# UniBot-PW01_V1_0.net
KiCad netlist of a schematic drawn in Altium Designer
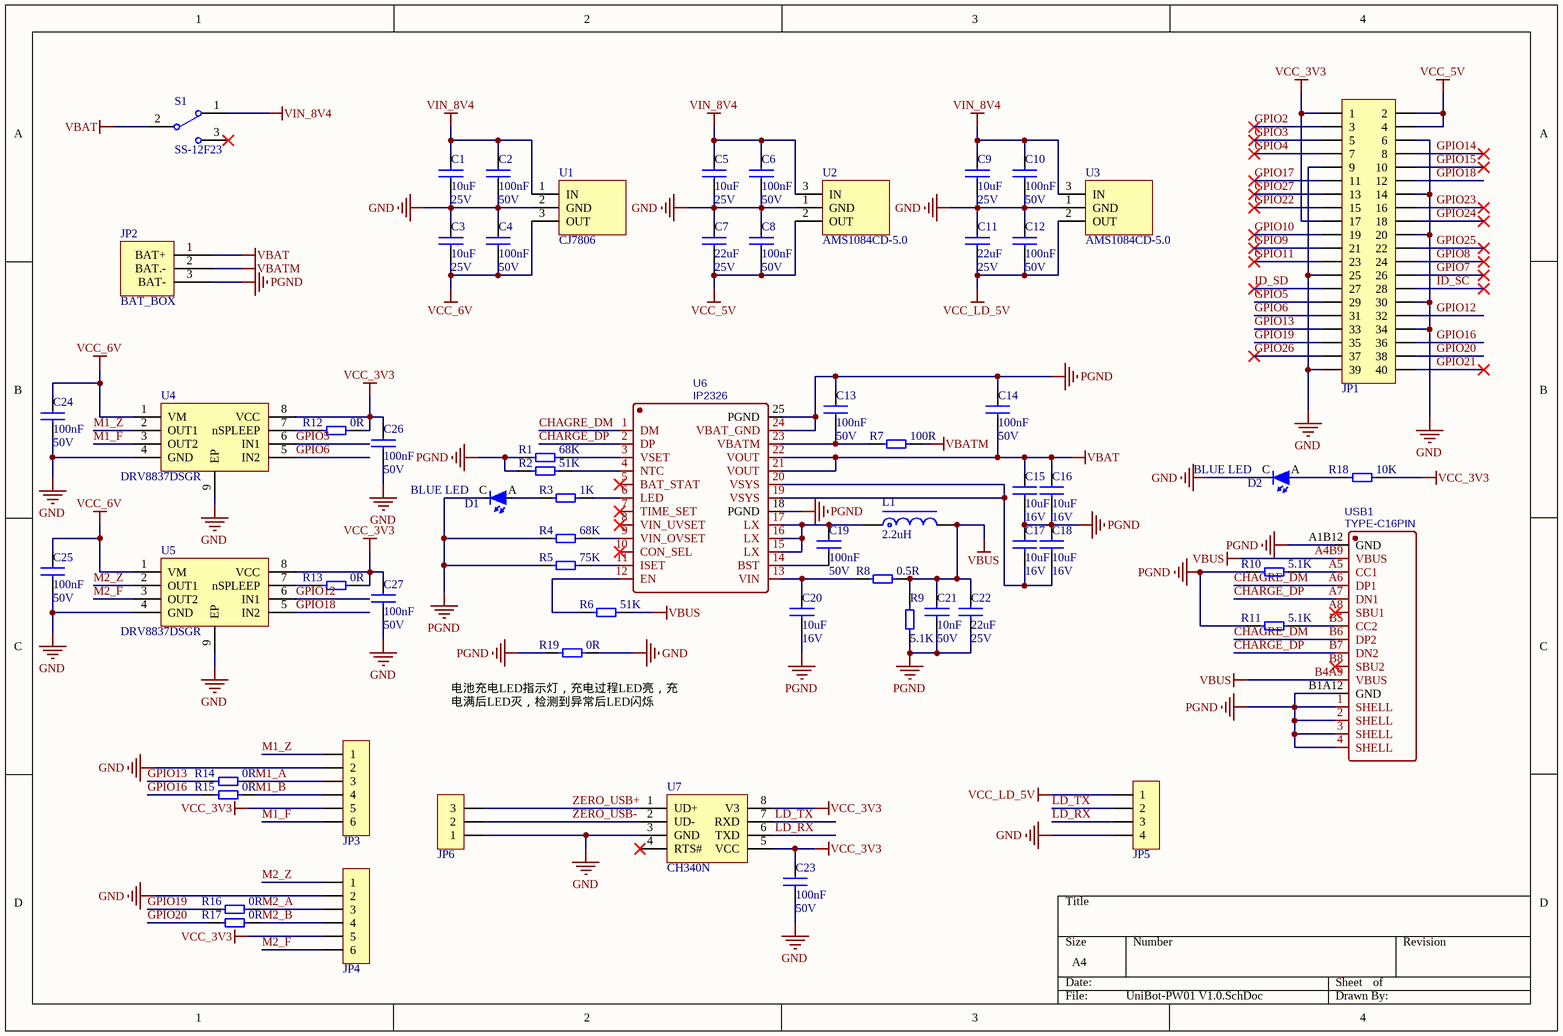
[diagram p0: UniBot-PW01 V1.0.SchDoc]

(export (version "E")
  (design (tool "Eeschema 10.0.6"))
  (components
    (comp (ref "C1")
      (value "10uF")
      (footprint "C0805")
      (description "CAP CER 10uF 25V X5R 0805")
      (fields
        (field (name "VOLTAGE") "25V")
        (field (name "PART NUMBER") "E01C00153")
        (field (name "POWER") "25V")
      )
      (libsource (lib "Database_Libs") (part "CAP NON POL"))
    )
    (comp (ref "C2")
      (value "100nF")
      (footprint "C0402")
      (description "CAP CER 100nF 50V X7R 0402")
      (fields
        (field (name "VOLTAGE") "50V")
        (field (name "PART NUMBER") "E01C00061")
        (field (name "POWER") "50V")
      )
      (libsource (lib "Database_Libs") (part "CAP NON POL"))
    )
    (comp (ref "C3")
      (value "10uF")
      (footprint "C0805")
      (description "CAP CER 10uF 25V X5R 0805")
      (fields
        (field (name "VOLTAGE") "25V")
        (field (name "PART NUMBER") "E01C00153")
        (field (name "POWER") "25V")
      )
      (libsource (lib "Database_Libs") (part "CAP NON POL"))
    )
    (comp (ref "C4")
      (value "100nF")
      (footprint "C0402")
      (description "CAP CER 100nF 50V X7R 0402")
      (fields
        (field (name "VOLTAGE") "50V")
        (field (name "PART NUMBER") "E01C00061")
        (field (name "POWER") "50V")
      )
      (libsource (lib "Database_Libs") (part "CAP NON POL"))
    )
    (comp (ref "C5")
      (value "10uF")
      (footprint "C0805")
      (description "CAP CER 10uF 25V X5R 0805")
      (fields
        (field (name "VOLTAGE") "25V")
        (field (name "PART NUMBER") "E01C00153")
        (field (name "POWER") "25V")
      )
      (libsource (lib "Database_Libs") (part "CAP NON POL"))
    )
    (comp (ref "C6")
      (value "100nF")
      (footprint "C0402")
      (description "CAP CER 100nF 50V X7R 0402")
      (fields
        (field (name "VOLTAGE") "50V")
        (field (name "PART NUMBER") "E01C00061")
        (field (name "POWER") "50V")
      )
      (libsource (lib "Database_Libs") (part "CAP NON POL"))
    )
    (comp (ref "C7")
      (value "22uF")
      (footprint "C0805")
      (description "CAP CER 22uF 25V X5R 0805")
      (fields
        (field (name "VOLTAGE") "25V")
        (field (name "PART NUMBER") "E01C00160")
        (field (name "POWER") "25V")
      )
      (libsource (lib "Database_Libs") (part "CAP NON POL"))
    )
    (comp (ref "C8")
      (value "100nF")
      (footprint "C0402")
      (description "CAP CER 100nF 50V X7R 0402")
      (fields
        (field (name "VOLTAGE") "50V")
        (field (name "PART NUMBER") "E01C00061")
        (field (name "POWER") "50V")
      )
      (libsource (lib "Database_Libs") (part "CAP NON POL"))
    )
    (comp (ref "C9")
      (value "10uF")
      (footprint "C0805")
      (description "CAP CER 10uF 25V X5R 0805")
      (fields
        (field (name "VOLTAGE") "25V")
        (field (name "PART NUMBER") "E01C00153")
        (field (name "POWER") "25V")
      )
      (libsource (lib "Database_Libs") (part "CAP NON POL"))
    )
    (comp (ref "C10")
      (value "100nF")
      (footprint "C0402")
      (description "CAP CER 100nF 50V X7R 0402")
      (fields
        (field (name "VOLTAGE") "50V")
        (field (name "PART NUMBER") "E01C00061")
        (field (name "POWER") "50V")
      )
      (libsource (lib "Database_Libs") (part "CAP NON POL"))
    )
    (comp (ref "C11")
      (value "22uF")
      (footprint "C0805")
      (description "CAP CER 22uF 25V X5R 0805")
      (fields
        (field (name "VOLTAGE") "25V")
        (field (name "PART NUMBER") "E01C00160")
        (field (name "POWER") "25V")
      )
      (libsource (lib "Database_Libs") (part "CAP NON POL"))
    )
    (comp (ref "C12")
      (value "100nF")
      (footprint "C0402")
      (description "CAP CER 100nF 50V X7R 0402")
      (fields
        (field (name "VOLTAGE") "50V")
        (field (name "PART NUMBER") "E01C00061")
        (field (name "POWER") "50V")
      )
      (libsource (lib "Database_Libs") (part "CAP NON POL"))
    )
    (comp (ref "C13")
      (value "100nF")
      (footprint "C0402")
      (description "CAP CER 100nF 50V X7R 0402")
      (fields
        (field (name "VOLTAGE") "50V")
        (field (name "PART NUMBER") "E01C00061")
        (field (name "POWER") "50V")
      )
      (libsource (lib "Database_Libs") (part "CAP NON POL"))
    )
    (comp (ref "C14")
      (value "100nF")
      (footprint "C0402")
      (description "CAP CER 100nF 50V X7R 0402")
      (fields
        (field (name "VOLTAGE") "50V")
        (field (name "PART NUMBER") "E01C00061")
        (field (name "POWER") "50V")
      )
      (libsource (lib "Database_Libs") (part "CAP NON POL"))
    )
    (comp (ref "C15")
      (value "10uF")
      (footprint "C0603")
      (description "CAP CER 10uF 16V X5R 0603")
      (fields
        (field (name "VOLTAGE") "16V")
        (field (name "PART NUMBER") "E01C00141")
        (field (name "POWER") "16V")
      )
      (libsource (lib "Database_Libs") (part "CAP NON POL"))
    )
    (comp (ref "C16")
      (value "10uF")
      (footprint "C0603")
      (description "CAP CER 10uF 16V X5R 0603")
      (fields
        (field (name "VOLTAGE") "16V")
        (field (name "PART NUMBER") "E01C00141")
        (field (name "POWER") "16V")
      )
      (libsource (lib "Database_Libs") (part "CAP NON POL"))
    )
    (comp (ref "C17")
      (value "10uF")
      (footprint "C0603")
      (description "CAP CER 10uF 16V X5R 0603")
      (fields
        (field (name "VOLTAGE") "16V")
        (field (name "PART NUMBER") "E01C00141")
        (field (name "POWER") "16V")
      )
      (libsource (lib "Database_Libs") (part "CAP NON POL"))
    )
    (comp (ref "C18")
      (value "10uF")
      (footprint "C0603")
      (description "CAP CER 10uF 16V X5R 0603")
      (fields
        (field (name "VOLTAGE") "16V")
        (field (name "PART NUMBER") "E01C00141")
        (field (name "POWER") "16V")
      )
      (libsource (lib "Database_Libs") (part "CAP NON POL"))
    )
    (comp (ref "C19")
      (value "100nF")
      (footprint "C0402")
      (description "CAP CER 100nF 50V X7R 0402")
      (fields
        (field (name "VOLTAGE") "50V")
        (field (name "PART NUMBER") "E01C00061")
        (field (name "POWER") "50V")
      )
      (libsource (lib "Database_Libs") (part "CAP NON POL"))
    )
    (comp (ref "C20")
      (value "10uF")
      (footprint "C0603")
      (description "CAP CER 10uF 16V X5R 0603")
      (fields
        (field (name "VOLTAGE") "16V")
        (field (name "PART NUMBER") "E01C00141")
        (field (name "POWER") "16V")
      )
      (libsource (lib "Database_Libs") (part "CAP NON POL"))
    )
    (comp (ref "C21")
      (value "10nF")
      (footprint "C0402")
      (description "CAP CER 10nF 50V X7R 0402")
      (fields
        (field (name "VOLTAGE") "50V")
        (field (name "PART NUMBER") "E01C00054")
        (field (name "POWER") "50V")
      )
      (libsource (lib "Database_Libs") (part "CAP NON POL"))
    )
    (comp (ref "C22")
      (value "22uF")
      (footprint "C0805")
      (description "CAP CER 22uF 25V X5R 0805")
      (fields
        (field (name "VOLTAGE") "25V")
        (field (name "PART NUMBER") "E01C00160")
        (field (name "POWER") "25V")
      )
      (libsource (lib "Database_Libs") (part "CAP NON POL"))
    )
    (comp (ref "C23")
      (value "100nF")
      (footprint "C0402")
      (description "CAP CER 100nF 50V X7R 0402")
      (fields
        (field (name "VOLTAGE") "50V")
        (field (name "PART NUMBER") "E01C00061")
        (field (name "POWER") "50V")
      )
      (libsource (lib "Database_Libs") (part "CAP NON POL"))
    )
    (comp (ref "C24")
      (value "100nF")
      (footprint "C0402")
      (description "CAP CER 100nF 50V X7R 0402")
      (fields
        (field (name "VOLTAGE") "50V")
        (field (name "PART NUMBER") "E01C00061")
        (field (name "POWER") "50V")
      )
      (libsource (lib "Database_Libs") (part "CAP NON POL"))
    )
    (comp (ref "C25")
      (value "100nF")
      (footprint "C0402")
      (description "CAP CER 100nF 50V X7R 0402")
      (fields
        (field (name "VOLTAGE") "50V")
        (field (name "PART NUMBER") "E01C00061")
        (field (name "POWER") "50V")
      )
      (libsource (lib "Database_Libs") (part "CAP NON POL"))
    )
    (comp (ref "C26")
      (value "100nF")
      (footprint "C0402")
      (description "CAP CER 100nF 50V X7R 0402")
      (fields
        (field (name "VOLTAGE") "50V")
        (field (name "PART NUMBER") "E01C00061")
        (field (name "POWER") "50V")
      )
      (libsource (lib "Database_Libs") (part "CAP NON POL"))
    )
    (comp (ref "C27")
      (value "100nF")
      (footprint "C0402")
      (description "CAP CER 100nF 50V X7R 0402")
      (fields
        (field (name "VOLTAGE") "50V")
        (field (name "PART NUMBER") "E01C00061")
        (field (name "POWER") "50V")
      )
      (libsource (lib "Database_Libs") (part "CAP NON POL"))
    )
    (comp (ref "D1")
      (value "BLUE LED")
      (footprint "LED-0402")
      (description "Blue led，20mcd@5mA")
      (fields (field (name "PART NUMBER") "E01D00010") (field (name "MFG") "BrtLed"))
      (libsource (lib "Database_Libs") (part "LED"))
    )
    (comp (ref "D2")
      (value "BLUE LED")
      (footprint "LED-0402")
      (description "Blue led，20mcd@5mA")
      (fields (field (name "PART NUMBER") "E01D00010") (field (name "MFG") "BrtLed"))
      (libsource (lib "Database_Libs") (part "LED"))
    )
    (comp (ref "JP1")
      (value "Header 2X11")
      (footprint "ZERO")
      (description "20*2P接插件")
      (fields (field (name "版权归属") "源创客"))
      (libsource (lib "4.6   - 接插件-脚距2.54") (part "Header 20X2"))
    )
    (comp (ref "JP2") (value "BAT_BOX") (footprint "BAT_BOX") (libsource (lib "Schlib1") (part "BAT_BOX")))
    (comp (ref "JP3")
      (value "HDR-1X6")
      (footprint "ZH1.5-WS-6P")
      (description "6P接插件")
      (fields (field (name "版权归属") "源创客"))
      (libsource (lib "4.4   - 接插件-脚距1.5") (part "Header 6"))
    )
    (comp (ref "JP4")
      (value "HDR-1X6")
      (footprint "ZH1.5-LS-6P")
      (description "6P接插件")
      (fields (field (name "版权归属") "源创客"))
      (libsource (lib "4.4   - 接插件-脚距1.5") (part "Header 6"))
    )
    (comp (ref "JP5")
      (value "HDR-1X4")
      (footprint "ZH1.5-LS-4P")
      (description "4P接插件")
      (fields (field (name "版权归属") "源创客"))
      (libsource (lib "4.4   - 接插件-脚距1.5") (part "Header 4"))
    )
    (comp (ref "JP6")
      (value "HDR-1X3")
      (footprint "ZH1.5-WS-3P")
      (description "3P接插件")
      (fields (field (name "版权归属") "源创客"))
      (libsource (lib "4.4   - 接插件-脚距1.5") (part "Header 3"))
    )
    (comp (ref "L1")
      (value "2.2uH")
      (footprint "NR5020")
      (description "TMPA0503S-2R2MN-D")
      (fields (field (name "版权归属") "源创客"))
      (libsource (lib "3.1   - 电阻-电容-电感") (part "L-CD"))
    )
    (comp (ref "R1")
      (value "68K")
      (footprint "R0402")
      (description "KES SMD 68K OHM 1% 1/16W 0402")
      (fields (field (name "PART NUMBER") "E01R00976") (field (name "POWER") "62.5mW,1/16W"))
      (libsource (lib "Database_Libs") (part "RES"))
    )
    (comp (ref "R2")
      (value "51K")
      (footprint "R0402")
      (description "KES SMD 51K OHM 1% 1/16W 0402")
      (fields (field (name "PART NUMBER") "E01R00977") (field (name "POWER") "62.5mW,1/16W"))
      (libsource (lib "Database_Libs") (part "RES"))
    )
    (comp (ref "R3")
      (value "1K")
      (footprint "R0402")
      (description "KES SMD 1K OHM 1% 1/16W 0402")
      (fields (field (name "PART NUMBER") "E01R00193") (field (name "POWER") "62.5mW，1/16W"))
      (libsource (lib "Database_Libs") (part "RES"))
    )
    (comp (ref "R4")
      (value "68K")
      (footprint "R0402")
      (description "KES SMD 68K OHM 1% 1/16W 0402")
      (fields (field (name "PART NUMBER") "E01R00976") (field (name "POWER") "62.5mW,1/16W"))
      (libsource (lib "Database_Libs") (part "RES"))
    )
    (comp (ref "R5")
      (value "75K")
      (footprint "R0402")
      (description "KES SMD 75K OHM 1% 1/16W 0402")
      (fields (field (name "PART NUMBER") "E01R00372") (field (name "POWER") "62.5mW，1/16W"))
      (libsource (lib "Database_Libs") (part "RES"))
    )
    (comp (ref "R6")
      (value "51K")
      (footprint "R0402")
      (description "KES SMD 51K OHM 1% 1/16W 0402")
      (fields (field (name "PART NUMBER") "E01R00977") (field (name "POWER") "62.5mW,1/16W"))
      (libsource (lib "Database_Libs") (part "RES"))
    )
    (comp (ref "R7")
      (value "100R")
      (footprint "R1206")
      (description "RES SMD 100R OHM 1% 1/4W 1206")
      (fields (field (name "PART NUMBER") "E01R00979") (field (name "POWER") "250mW, 1/4W"))
      (libsource (lib "Database_Libs") (part "RES"))
    )
    (comp (ref "R8")
      (value "0.5R")
      (footprint "R0603")
      (description "RES SMD 0.5R OHM 1& 1/10W 0603")
      (fields (field (name "PART NUMBER") "E01R00980") (field (name "POWER") "100mW, 1/10W"))
      (libsource (lib "Database_Libs") (part "RES"))
    )
    (comp (ref "R9")
      (value "5.1K")
      (footprint "R0603")
      (description "KES SMD 5.1K OHM 1% 1/10W 0603")
      (fields (field (name "PART NUMBER") "E01R00981") (field (name "POWER") "100mW, 1/10W"))
      (libsource (lib "") (part "RES_1"))
    )
    (comp (ref "R10")
      (value "5.1K")
      (footprint "R0603")
      (description "KES SMD 5.1K OHM 1% 1/10W 0603")
      (fields (field (name "PART NUMBER") "E01R00981") (field (name "POWER") "100mW, 1/10W"))
      (libsource (lib "Database_Libs") (part "RES"))
    )
    (comp (ref "R11")
      (value "5.1K")
      (footprint "R0603")
      (description "KES SMD 5.1K OHM 1% 1/10W 0603")
      (fields (field (name "PART NUMBER") "E01R00981") (field (name "POWER") "100mW, 1/10W"))
      (libsource (lib "Database_Libs") (part "RES"))
    )
    (comp (ref "R12")
      (value "0R")
      (footprint "R0402")
      (description "RES SMD 0R OHM 1% 1/16W 0402")
      (fields (field (name "PART NUMBER") "E01R00001") (field (name "POWER") "62.5mW，1/16W"))
      (libsource (lib "Database_Libs") (part "RES"))
    )
    (comp (ref "R13")
      (value "0R")
      (footprint "R0402")
      (description "RES SMD 0R OHM 1% 1/16W 0402")
      (fields (field (name "PART NUMBER") "E01R00001") (field (name "POWER") "62.5mW，1/16W"))
      (libsource (lib "Database_Libs") (part "RES"))
    )
    (comp (ref "R14")
      (value "0R")
      (footprint "R0402")
      (description "RES SMD 0R OHM 1% 1/16W 0402")
      (fields (field (name "PART NUMBER") "E01R00001") (field (name "POWER") "62.5mW，1/16W"))
      (libsource (lib "Database_Libs") (part "RES"))
    )
    (comp (ref "R15")
      (value "0R")
      (footprint "R0402")
      (description "RES SMD 0R OHM 1% 1/16W 0402")
      (fields (field (name "PART NUMBER") "E01R00001") (field (name "POWER") "62.5mW，1/16W"))
      (libsource (lib "Database_Libs") (part "RES"))
    )
    (comp (ref "R16")
      (value "0R")
      (footprint "R0402")
      (description "RES SMD 0R OHM 1% 1/16W 0402")
      (fields (field (name "PART NUMBER") "E01R00001") (field (name "POWER") "62.5mW，1/16W"))
      (libsource (lib "Database_Libs") (part "RES"))
    )
    (comp (ref "R17")
      (value "0R")
      (footprint "R0402")
      (description "RES SMD 0R OHM 1% 1/16W 0402")
      (fields (field (name "PART NUMBER") "E01R00001") (field (name "POWER") "62.5mW，1/16W"))
      (libsource (lib "Database_Libs") (part "RES"))
    )
    (comp (ref "R18")
      (value "10K")
      (footprint "R0402")
      (description "KES SMD 10K OHM 0.1% 1/16W 0402")
      (fields (field (name "PART NUMBER") "E01R00975") (field (name "POWER") "62.5mW,1/16W"))
      (libsource (lib "Database_Libs") (part "RES"))
    )
    (comp (ref "R19")
      (value "0R")
      (footprint "R0805")
      (description "RES SMD 0R OHM 1% 1/8W 0805")
      (fields (field (name "PART NUMBER") "E01R00973") (field (name "POWER") "125mW，1/8W"))
      (libsource (lib "Database_Libs") (part "RES"))
    )
    (comp (ref "S1")
      (value "SS-12F23")
      (footprint "SS-12F23")
      (description "1路波动开关")
      (fields (field (name "版权归属") "源创客"))
      (libsource (lib "5.1   - 按键-开关") (part "SSW-1P"))
    )
    (comp (ref "U1") (value "CJ7806") (footprint "TO252") (libsource (lib "Schlib1") (part "CJ7806")))
    (comp (ref "U2") (value "AMS1084CD-5.0") (footprint "TO252") (libsource (lib "Schlib1") (part "CJ7805")))
    (comp (ref "U3") (value "AMS1084CD-5.0") (footprint "TO252") (libsource (lib "Schlib1") (part "CJ7805")))
    (comp (ref "U4")
      (value "DRV8837DSGR")
      (footprint "DRV8837DSGR")
      (libsource (lib "Schlib1") (part "DRV8837DSGR"))
    )
    (comp (ref "U5")
      (value "DRV8837DSGR")
      (footprint "DRV8837DSGR")
      (libsource (lib "Schlib1") (part "DRV8837DSGR"))
    )
    (comp (ref "U6")
      (value "IP2326")
      (footprint "QFN:QFN24 4x4_L")
      (fields (field (name "MANUFACTURER") "Injoinic") (field (name "CONTRIBUTOR") "JustBlackQ"))
      (libsource (lib "altium-import") (part "root_0_IP2326_"))
    )
    (comp (ref "U7")
      (value "CH340N")
      (footprint "SOP8_L")
      (description "USB转TTL芯片")
      (libsource (lib "Schlib1") (part "CH340N"))
    )
    (comp (ref "USB1")
      (value "TYPE-C16PIN")
      (footprint "U262-16XN-4BVC11")
      (fields (field (name "MANUFACTURER") "SHOU HAN") (field (name "CONTRIBUTOR") "LCSC"))
      (libsource (lib "altium-import") (part "root_0_TYPE-C16PIN_"))
    )
  )
  (nets
    (net (code "1") (name "/CHAGRE_DM") (class "Default")
      (node (ref "U6") (pin "1") (pinfunction "DM_1") (pintype "passive"))
      (node (ref "USB1") (pin "A6") (pinfunction "DP1_A6") (pintype "passive"))
      (node (ref "USB1") (pin "B6") (pinfunction "DP2_B6") (pintype "passive"))
    )
    (net (code "2") (name "/CHARGE_DP") (class "Default")
      (node (ref "U6") (pin "2") (pinfunction "DP_2") (pintype "passive"))
      (node (ref "USB1") (pin "A7") (pinfunction "DN1_A7") (pintype "passive"))
      (node (ref "USB1") (pin "B7") (pinfunction "DN2_B7") (pintype "passive"))
    )
    (net (code "3") (name "/GPIO2") (class "Default")
      (node (ref "JP1") (pin "3") (pinfunction "3_3") (pintype "passive+no_connect"))
    )
    (net (code "4") (name "/GPIO3") (class "Default")
      (node (ref "JP1") (pin "5") (pinfunction "5_5") (pintype "passive+no_connect"))
    )
    (net (code "5") (name "/GPIO4") (class "Default")
      (node (ref "JP1") (pin "7") (pinfunction "7_7") (pintype "passive+no_connect"))
    )
    (net (code "6") (name "/GPIO5") (class "Default")
      (node (ref "JP1") (pin "29") (pinfunction "29_29") (pintype "passive"))
      (node (ref "U4") (pin "6") (pinfunction "IN1_6") (pintype "passive"))
    )
    (net (code "7") (name "/GPIO6") (class "Default")
      (node (ref "JP1") (pin "31") (pinfunction "31_31") (pintype "passive"))
      (node (ref "U4") (pin "5") (pinfunction "IN2_5") (pintype "passive"))
    )
    (net (code "8") (name "/GPIO7") (class "Default")
      (node (ref "JP1") (pin "26") (pinfunction "26_26") (pintype "passive+no_connect"))
    )
    (net (code "9") (name "/GPIO8") (class "Default")
      (node (ref "JP1") (pin "24") (pinfunction "24_24") (pintype "passive+no_connect"))
    )
    (net (code "10") (name "/GPIO9") (class "Default")
      (node (ref "JP1") (pin "21") (pinfunction "21_21") (pintype "passive+no_connect"))
    )
    (net (code "11") (name "/GPIO10") (class "Default")
      (node (ref "JP1") (pin "19") (pinfunction "19_19") (pintype "passive+no_connect"))
    )
    (net (code "12") (name "/GPIO11") (class "Default")
      (node (ref "JP1") (pin "23") (pinfunction "23_23") (pintype "passive+no_connect"))
    )
    (net (code "13") (name "/GPIO12") (class "Default")
      (node (ref "JP1") (pin "32") (pinfunction "32_32") (pintype "passive"))
      (node (ref "U5") (pin "6") (pinfunction "IN1_6") (pintype "passive"))
    )
    (net (code "14") (name "/GPIO13") (class "Default")
      (node (ref "JP1") (pin "33") (pinfunction "33_33") (pintype "passive"))
      (node (ref "R14") (pin "1") (pinfunction "1_1") (pintype "passive"))
    )
    (net (code "15") (name "/GPIO14") (class "Default")
      (node (ref "JP1") (pin "8") (pinfunction "8_8") (pintype "passive+no_connect"))
    )
    (net (code "16") (name "/GPIO15") (class "Default")
      (node (ref "JP1") (pin "10") (pinfunction "10_10") (pintype "passive+no_connect"))
    )
    (net (code "17") (name "/GPIO16") (class "Default")
      (node (ref "JP1") (pin "36") (pinfunction "36_36") (pintype "passive"))
      (node (ref "R15") (pin "1") (pinfunction "1_1") (pintype "passive"))
    )
    (net (code "18") (name "/GPIO17") (class "Default")
      (node (ref "JP1") (pin "11") (pinfunction "11_11") (pintype "passive+no_connect"))
    )
    (net (code "19") (name "/GPIO18") (class "Default")
      (node (ref "JP1") (pin "12") (pinfunction "12_12") (pintype "passive"))
      (node (ref "U5") (pin "5") (pinfunction "IN2_5") (pintype "passive"))
    )
    (net (code "20") (name "/GPIO19") (class "Default")
      (node (ref "JP1") (pin "35") (pinfunction "35_35") (pintype "passive"))
      (node (ref "R16") (pin "1") (pinfunction "1_1") (pintype "passive"))
    )
    (net (code "21") (name "/GPIO20") (class "Default")
      (node (ref "JP1") (pin "38") (pinfunction "38_38") (pintype "passive"))
      (node (ref "R17") (pin "1") (pinfunction "1_1") (pintype "passive"))
    )
    (net (code "22") (name "/GPIO21") (class "Default")
      (node (ref "JP1") (pin "40") (pinfunction "40_40") (pintype "passive+no_connect"))
    )
    (net (code "23") (name "/GPIO22") (class "Default")
      (node (ref "JP1") (pin "15") (pinfunction "15_15") (pintype "passive+no_connect"))
    )
    (net (code "24") (name "/GPIO23") (class "Default")
      (node (ref "JP1") (pin "16") (pinfunction "16_16") (pintype "passive+no_connect"))
    )
    (net (code "25") (name "/GPIO24") (class "Default")
      (node (ref "JP1") (pin "18") (pinfunction "18_18") (pintype "passive+no_connect"))
    )
    (net (code "26") (name "/GPIO25") (class "Default")
      (node (ref "JP1") (pin "22") (pinfunction "22_22") (pintype "passive+no_connect"))
    )
    (net (code "27") (name "/GPIO26") (class "Default")
      (node (ref "JP1") (pin "37") (pinfunction "37_37") (pintype "passive+no_connect"))
    )
    (net (code "28") (name "/GPIO27") (class "Default")
      (node (ref "JP1") (pin "13") (pinfunction "13_13") (pintype "passive+no_connect"))
    )
    (net (code "29") (name "/ID_SC") (class "Default")
      (node (ref "JP1") (pin "28") (pinfunction "28_28") (pintype "passive+no_connect"))
    )
    (net (code "30") (name "/ID_SD") (class "Default")
      (node (ref "JP1") (pin "27") (pinfunction "27_27") (pintype "passive+no_connect"))
    )
    (net (code "31") (name "/LD_RX") (class "Default")
      (node (ref "JP5") (pin "3") (pinfunction "3_3") (pintype "passive"))
      (node (ref "U7") (pin "6") (pinfunction "TXD_6") (pintype "passive"))
    )
    (net (code "32") (name "/LD_TX") (class "Default")
      (node (ref "JP5") (pin "2") (pinfunction "2_2") (pintype "passive"))
      (node (ref "U7") (pin "7") (pinfunction "RXD_7") (pintype "passive"))
    )
    (net (code "33") (name "/M1_A") (class "Default")
      (node (ref "JP3") (pin "3") (pinfunction "3_3") (pintype "passive"))
      (node (ref "R14") (pin "2") (pinfunction "2_2") (pintype "passive"))
    )
    (net (code "34") (name "/M1_B") (class "Default")
      (node (ref "JP3") (pin "4") (pinfunction "4_4") (pintype "passive"))
      (node (ref "R15") (pin "2") (pinfunction "2_2") (pintype "passive"))
    )
    (net (code "35") (name "/M1_F") (class "Default")
      (node (ref "JP3") (pin "6") (pinfunction "6_6") (pintype "passive"))
      (node (ref "U4") (pin "3") (pinfunction "OUT2_3") (pintype "passive"))
    )
    (net (code "36") (name "/M1_Z") (class "Default")
      (node (ref "JP3") (pin "1") (pinfunction "1_1") (pintype "passive"))
      (node (ref "U4") (pin "2") (pinfunction "OUT1_2") (pintype "passive"))
    )
    (net (code "37") (name "/M2_A") (class "Default")
      (node (ref "JP4") (pin "3") (pinfunction "3_3") (pintype "passive"))
      (node (ref "R16") (pin "2") (pinfunction "2_2") (pintype "passive"))
    )
    (net (code "38") (name "/M2_B") (class "Default")
      (node (ref "JP4") (pin "4") (pinfunction "4_4") (pintype "passive"))
      (node (ref "R17") (pin "2") (pinfunction "2_2") (pintype "passive"))
    )
    (net (code "39") (name "/M2_F") (class "Default")
      (node (ref "JP4") (pin "6") (pinfunction "6_6") (pintype "passive"))
      (node (ref "U5") (pin "3") (pinfunction "OUT2_3") (pintype "passive"))
    )
    (net (code "40") (name "/M2_Z") (class "Default")
      (node (ref "JP4") (pin "1") (pinfunction "1_1") (pintype "passive"))
      (node (ref "U5") (pin "2") (pinfunction "OUT1_2") (pintype "passive"))
    )
    (net (code "41") (name "/ZERO_USB+") (class "Default")
      (node (ref "JP6") (pin "3") (pinfunction "3_3") (pintype "passive"))
      (node (ref "U7") (pin "1") (pinfunction "UD+_1") (pintype "passive"))
    )
    (net (code "42") (name "/ZERO_USB-") (class "Default")
      (node (ref "JP6") (pin "2") (pinfunction "2_2") (pintype "passive"))
      (node (ref "U7") (pin "2") (pinfunction "UD-_2") (pintype "passive"))
    )
    (net (code "43") (name "GND") (class "Default")
      (node (ref "C1") (pin "2") (pinfunction "2_2") (pintype "passive"))
      (node (ref "C10") (pin "2") (pinfunction "2_2") (pintype "passive"))
      (node (ref "C11") (pin "1") (pinfunction "1_1") (pintype "passive"))
      (node (ref "C12") (pin "1") (pinfunction "1_1") (pintype "passive"))
      (node (ref "C2") (pin "2") (pinfunction "2_2") (pintype "passive"))
      (node (ref "C23") (pin "2") (pinfunction "2_2") (pintype "passive"))
      (node (ref "C24") (pin "2") (pinfunction "2_2") (pintype "passive"))
      (node (ref "C25") (pin "2") (pinfunction "2_2") (pintype "passive"))
      (node (ref "C26") (pin "2") (pinfunction "2_2") (pintype "passive"))
      (node (ref "C27") (pin "2") (pinfunction "2_2") (pintype "passive"))
      (node (ref "C3") (pin "1") (pinfunction "1_1") (pintype "passive"))
      (node (ref "C4") (pin "1") (pinfunction "1_1") (pintype "passive"))
      (node (ref "C5") (pin "2") (pinfunction "2_2") (pintype "passive"))
      (node (ref "C6") (pin "2") (pinfunction "2_2") (pintype "passive"))
      (node (ref "C7") (pin "1") (pinfunction "1_1") (pintype "passive"))
      (node (ref "C8") (pin "1") (pinfunction "1_1") (pintype "passive"))
      (node (ref "C9") (pin "2") (pinfunction "2_2") (pintype "passive"))
      (node (ref "D2") (pin "C") (pinfunction "C_C") (pintype "passive"))
      (node (ref "JP1") (pin "14") (pinfunction "14_14") (pintype "passive"))
      (node (ref "JP1") (pin "20") (pinfunction "20_20") (pintype "passive"))
      (node (ref "JP1") (pin "25") (pinfunction "25_25") (pintype "passive"))
      (node (ref "JP1") (pin "30") (pinfunction "30_30") (pintype "passive"))
      (node (ref "JP1") (pin "34") (pinfunction "34_34") (pintype "passive"))
      (node (ref "JP1") (pin "39") (pinfunction "39_39") (pintype "passive"))
      (node (ref "JP1") (pin "6") (pinfunction "6_6") (pintype "passive"))
      (node (ref "JP1") (pin "9") (pinfunction "9_9") (pintype "passive"))
      (node (ref "JP3") (pin "2") (pinfunction "2_2") (pintype "passive"))
      (node (ref "JP4") (pin "2") (pinfunction "2_2") (pintype "passive"))
      (node (ref "JP5") (pin "4") (pinfunction "4_4") (pintype "passive"))
      (node (ref "JP6") (pin "1") (pinfunction "1_1") (pintype "passive"))
      (node (ref "R19") (pin "2") (pinfunction "2_2") (pintype "passive"))
      (node (ref "U1") (pin "2") (pinfunction "GND_2") (pintype "passive"))
      (node (ref "U2") (pin "1") (pinfunction "GND_1") (pintype "passive"))
      (node (ref "U3") (pin "1") (pinfunction "GND_1") (pintype "passive"))
      (node (ref "U4") (pin "4") (pinfunction "GND_4") (pintype "passive"))
      (node (ref "U4") (pin "9") (pinfunction "EP_9") (pintype "passive"))
      (node (ref "U5") (pin "4") (pinfunction "GND_4") (pintype "passive"))
      (node (ref "U5") (pin "9") (pinfunction "EP_9") (pintype "passive"))
      (node (ref "U7") (pin "3") (pinfunction "GND_3") (pintype "passive"))
    )
    (net (code "44") (name "Net-(C17-Pad2)") (class "Default")
      (node (ref "C17") (pin "2") (pinfunction "2_2") (pintype "passive"))
      (node (ref "C18") (pin "2") (pinfunction "2_2") (pintype "passive"))
      (node (ref "U6") (pin "19") (pinfunction "VSYS_19") (pintype "passive"))
      (node (ref "U6") (pin "20") (pinfunction "VSYS_20") (pintype "passive"))
    )
    (net (code "45") (name "Net-(C19-Pad1)") (class "Default")
      (node (ref "C19") (pin "1") (pinfunction "1_1") (pintype "passive"))
      (node (ref "L1") (pin "1") (pinfunction "1_1") (pintype "passive"))
      (node (ref "U6") (pin "15") (pinfunction "LX_15") (pintype "passive"))
      (node (ref "U6") (pin "16") (pinfunction "LX_16") (pintype "passive"))
      (node (ref "U6") (pin "17") (pinfunction "LX_17") (pintype "passive"))
    )
    (net (code "46") (name "Net-(D1-PadA)") (class "Default")
      (node (ref "D1") (pin "A") (pinfunction "A_A") (pintype "passive"))
      (node (ref "R3") (pin "1") (pinfunction "1_1") (pintype "passive"))
    )
    (net (code "47") (name "Net-(D2-PadA)") (class "Default")
      (node (ref "D2") (pin "A") (pinfunction "A_A") (pintype "passive"))
      (node (ref "R18") (pin "1") (pinfunction "1_1") (pintype "passive"))
    )
    (net (code "48") (name "Net-(U4-nSPLEEP)") (class "Default")
      (node (ref "R12") (pin "1") (pinfunction "1_1") (pintype "passive"))
      (node (ref "U4") (pin "7") (pinfunction "nSPLEEP_7") (pintype "passive"))
    )
    (net (code "49") (name "Net-(U5-nSPLEEP)") (class "Default")
      (node (ref "R13") (pin "1") (pinfunction "1_1") (pintype "passive"))
      (node (ref "U5") (pin "7") (pinfunction "nSPLEEP_7") (pintype "passive"))
    )
    (net (code "50") (name "Net-(U6-BST)") (class "Default")
      (node (ref "C19") (pin "2") (pinfunction "2_2") (pintype "passive"))
      (node (ref "U6") (pin "14") (pinfunction "BST_14") (pintype "passive"))
    )
    (net (code "51") (name "Net-(U6-EN)") (class "Default")
      (node (ref "R6") (pin "1") (pinfunction "1_1") (pintype "passive"))
      (node (ref "U6") (pin "12") (pinfunction "EN_12") (pintype "passive"))
    )
    (net (code "52") (name "Net-(U6-ISET)") (class "Default")
      (node (ref "R5") (pin "2") (pinfunction "2_2") (pintype "passive"))
      (node (ref "U6") (pin "11") (pinfunction "ISET_11") (pintype "passive"))
    )
    (net (code "53") (name "Net-(U6-LED)") (class "Default")
      (node (ref "R3") (pin "2") (pinfunction "2_2") (pintype "passive"))
      (node (ref "U6") (pin "6") (pinfunction "LED_6") (pintype "passive"))
    )
    (net (code "54") (name "Net-(U6-NTC)") (class "Default")
      (node (ref "R2") (pin "2") (pinfunction "2_2") (pintype "passive"))
      (node (ref "U6") (pin "4") (pinfunction "NTC_4") (pintype "passive"))
    )
    (net (code "55") (name "Net-(U6-VBATM)") (class "Default")
      (node (ref "C13") (pin "2") (pinfunction "2_2") (pintype "passive"))
      (node (ref "R7") (pin "1") (pinfunction "1_1") (pintype "passive"))
      (node (ref "U6") (pin "23") (pinfunction "VBATM_23") (pintype "passive"))
    )
    (net (code "56") (name "Net-(U6-VIN)") (class "Default")
      (node (ref "C20") (pin "1") (pinfunction "1_1") (pintype "passive"))
      (node (ref "R8") (pin "1") (pinfunction "1_1") (pintype "passive"))
      (node (ref "U6") (pin "13") (pinfunction "VIN_13") (pintype "passive"))
    )
    (net (code "57") (name "Net-(U6-VIN_OVSET)") (class "Default")
      (node (ref "R4") (pin "2") (pinfunction "2_2") (pintype "passive"))
      (node (ref "U6") (pin "9") (pinfunction "VIN_OVSET_9") (pintype "passive"))
    )
    (net (code "58") (name "Net-(U6-VSET)") (class "Default")
      (node (ref "R1") (pin "2") (pinfunction "2_2") (pintype "passive"))
      (node (ref "U6") (pin "3") (pinfunction "VSET_3") (pintype "passive"))
    )
    (net (code "59") (name "Net-(USB1-CC1)") (class "Default")
      (node (ref "R10") (pin "2") (pinfunction "2_2") (pintype "passive"))
      (node (ref "USB1") (pin "A5") (pinfunction "CC1_A5") (pintype "passive"))
    )
    (net (code "60") (name "Net-(USB1-CC2)") (class "Default")
      (node (ref "R11") (pin "2") (pinfunction "2_2") (pintype "passive"))
      (node (ref "USB1") (pin "B5") (pinfunction "CC2_B5") (pintype "passive"))
    )
    (net (code "61") (name "PGND") (class "Default")
      (node (ref "C13") (pin "1") (pinfunction "1_1") (pintype "passive"))
      (node (ref "C14") (pin "1") (pinfunction "1_1") (pintype "passive"))
      (node (ref "C15") (pin "2") (pinfunction "2_2") (pintype "passive"))
      (node (ref "C16") (pin "2") (pinfunction "2_2") (pintype "passive"))
      (node (ref "C17") (pin "1") (pinfunction "1_1") (pintype "passive"))
      (node (ref "C18") (pin "1") (pinfunction "1_1") (pintype "passive"))
      (node (ref "C20") (pin "2") (pinfunction "2_2") (pintype "passive"))
      (node (ref "C21") (pin "2") (pinfunction "2_2") (pintype "passive"))
      (node (ref "C22") (pin "2") (pinfunction "2_2") (pintype "passive"))
      (node (ref "D1") (pin "C") (pinfunction "C_C") (pintype "passive"))
      (node (ref "JP2") (pin "3") (pinfunction "BAT-_3") (pintype "passive"))
      (node (ref "R1") (pin "1") (pinfunction "1_1") (pintype "passive"))
      (node (ref "R10") (pin "1") (pinfunction "1_1") (pintype "passive"))
      (node (ref "R11") (pin "1") (pinfunction "1_1") (pintype "passive"))
      (node (ref "R19") (pin "1") (pinfunction "1_1") (pintype "passive"))
      (node (ref "R2") (pin "1") (pinfunction "1_1") (pintype "passive"))
      (node (ref "R4") (pin "1") (pinfunction "1_1") (pintype "passive"))
      (node (ref "R5") (pin "1") (pinfunction "1_1") (pintype "passive"))
      (node (ref "R9") (pin "2") (pinfunction "2_2") (pintype "passive"))
      (node (ref "U6") (pin "18") (pinfunction "PGND_18") (pintype "passive"))
      (node (ref "U6") (pin "24") (pinfunction "VBAT_GND_24") (pintype "passive"))
      (node (ref "U6") (pin "25") (pinfunction "PGND_25") (pintype "passive"))
      (node (ref "USB1") (pin "1") (pinfunction "SHELL_1") (pintype "passive"))
      (node (ref "USB1") (pin "2") (pinfunction "SHELL_2") (pintype "passive"))
      (node (ref "USB1") (pin "3") (pinfunction "SHELL_3") (pintype "passive"))
      (node (ref "USB1") (pin "4") (pinfunction "SHELL_4") (pintype "passive"))
      (node (ref "USB1") (pin "A1B12") (pinfunction "GND_A1B12") (pintype "passive"))
      (node (ref "USB1") (pin "B1A12") (pinfunction "GND_B1A12") (pintype "passive"))
    )
    (net (code "62") (name "VBAT") (class "Default")
      (node (ref "C14") (pin "2") (pinfunction "2_2") (pintype "passive"))
      (node (ref "C15") (pin "1") (pinfunction "1_1") (pintype "passive"))
      (node (ref "C16") (pin "1") (pinfunction "1_1") (pintype "passive"))
      (node (ref "JP2") (pin "1") (pinfunction "BAT+_1") (pintype "passive"))
      (node (ref "S1") (pin "2") (pinfunction "2_2") (pintype "passive"))
      (node (ref "U6") (pin "21") (pinfunction "VOUT_21") (pintype "passive"))
      (node (ref "U6") (pin "22") (pinfunction "VOUT_22") (pintype "passive"))
    )
    (net (code "63") (name "VBATM") (class "Default")
      (node (ref "JP2") (pin "2") (pinfunction "BAT.-_2") (pintype "passive"))
      (node (ref "R7") (pin "2") (pinfunction "2_2") (pintype "passive"))
    )
    (net (code "64") (name "VBUS") (class "Default")
      (node (ref "C21") (pin "1") (pinfunction "1_1") (pintype "passive"))
      (node (ref "C22") (pin "1") (pinfunction "1_1") (pintype "passive"))
      (node (ref "L1") (pin "2") (pinfunction "2_2") (pintype "passive"))
      (node (ref "R6") (pin "2") (pinfunction "2_2") (pintype "passive"))
      (node (ref "R8") (pin "2") (pinfunction "2_2") (pintype "passive"))
      (node (ref "R9") (pin "1") (pinfunction "1_1") (pintype "passive"))
      (node (ref "USB1") (pin "A4B9") (pinfunction "VBUS_A4B9") (pintype "passive"))
      (node (ref "USB1") (pin "B4A9") (pinfunction "VBUS_B4A9") (pintype "passive"))
    )
    (net (code "65") (name "VCC_3V3") (class "Default")
      (node (ref "C23") (pin "1") (pinfunction "1_1") (pintype "passive"))
      (node (ref "C26") (pin "1") (pinfunction "1_1") (pintype "passive"))
      (node (ref "C27") (pin "1") (pinfunction "1_1") (pintype "passive"))
      (node (ref "JP1") (pin "1") (pinfunction "1_1") (pintype "passive"))
      (node (ref "JP1") (pin "17") (pinfunction "17_17") (pintype "passive"))
      (node (ref "JP3") (pin "5") (pinfunction "5_5") (pintype "passive"))
      (node (ref "JP4") (pin "5") (pinfunction "5_5") (pintype "passive"))
      (node (ref "R12") (pin "2") (pinfunction "2_2") (pintype "passive"))
      (node (ref "R13") (pin "2") (pinfunction "2_2") (pintype "passive"))
      (node (ref "R18") (pin "2") (pinfunction "2_2") (pintype "passive"))
      (node (ref "U4") (pin "8") (pinfunction "VCC_8") (pintype "passive"))
      (node (ref "U5") (pin "8") (pinfunction "VCC_8") (pintype "passive"))
      (node (ref "U7") (pin "5") (pinfunction "VCC_5") (pintype "passive"))
      (node (ref "U7") (pin "8") (pinfunction "V3_8") (pintype "passive"))
    )
    (net (code "66") (name "VCC_5V") (class "Default")
      (node (ref "C7") (pin "2") (pinfunction "2_2") (pintype "passive"))
      (node (ref "C8") (pin "2") (pinfunction "2_2") (pintype "passive"))
      (node (ref "JP1") (pin "2") (pinfunction "2_2") (pintype "passive"))
      (node (ref "JP1") (pin "4") (pinfunction "4_4") (pintype "passive"))
      (node (ref "U2") (pin "2") (pinfunction "OUT_2") (pintype "passive"))
    )
    (net (code "67") (name "VCC_6V") (class "Default")
      (node (ref "C24") (pin "1") (pinfunction "1_1") (pintype "passive"))
      (node (ref "C25") (pin "1") (pinfunction "1_1") (pintype "passive"))
      (node (ref "C3") (pin "2") (pinfunction "2_2") (pintype "passive"))
      (node (ref "C4") (pin "2") (pinfunction "2_2") (pintype "passive"))
      (node (ref "U1") (pin "3") (pinfunction "OUT_3") (pintype "passive"))
      (node (ref "U4") (pin "1") (pinfunction "VM_1") (pintype "passive"))
      (node (ref "U5") (pin "1") (pinfunction "VM_1") (pintype "passive"))
    )
    (net (code "68") (name "VCC_LD_5V") (class "Default")
      (node (ref "C11") (pin "2") (pinfunction "2_2") (pintype "passive"))
      (node (ref "C12") (pin "2") (pinfunction "2_2") (pintype "passive"))
      (node (ref "JP5") (pin "1") (pinfunction "1_1") (pintype "passive"))
      (node (ref "U3") (pin "2") (pinfunction "OUT_2") (pintype "passive"))
    )
    (net (code "69") (name "VIN_8V4") (class "Default")
      (node (ref "C1") (pin "1") (pinfunction "1_1") (pintype "passive"))
      (node (ref "C10") (pin "1") (pinfunction "1_1") (pintype "passive"))
      (node (ref "C2") (pin "1") (pinfunction "1_1") (pintype "passive"))
      (node (ref "C5") (pin "1") (pinfunction "1_1") (pintype "passive"))
      (node (ref "C6") (pin "1") (pinfunction "1_1") (pintype "passive"))
      (node (ref "C9") (pin "1") (pinfunction "1_1") (pintype "passive"))
      (node (ref "S1") (pin "1") (pinfunction "1_1") (pintype "passive"))
      (node (ref "U1") (pin "1") (pinfunction "IN_1") (pintype "passive"))
      (node (ref "U2") (pin "3") (pinfunction "IN_3") (pintype "passive"))
      (node (ref "U3") (pin "3") (pinfunction "IN_3") (pintype "passive"))
    )
    (net (code "70") (name "unconnected-(S1-Pad3)") (class "Default")
      (node (ref "S1") (pin "3") (pinfunction "3_3") (pintype "passive+no_connect"))
    )
    (net (code "71") (name "unconnected-(U6-BAT_STAT-Pad5)") (class "Default")
      (node (ref "U6") (pin "5") (pinfunction "BAT_STAT_5") (pintype "passive+no_connect"))
    )
    (net (code "72") (name "unconnected-(U6-CON_SEL-Pad10)") (class "Default")
      (node (ref "U6") (pin "10") (pinfunction "CON_SEL_10") (pintype "passive+no_connect"))
    )
    (net (code "73") (name "unconnected-(U6-TIME_SET-Pad7)") (class "Default")
      (node (ref "U6") (pin "7") (pinfunction "TIME_SET_7") (pintype "passive+no_connect"))
    )
    (net (code "74") (name "unconnected-(U6-VIN_UVSET-Pad8)") (class "Default")
      (node (ref "U6") (pin "8") (pinfunction "VIN_UVSET_8") (pintype "passive+no_connect"))
    )
    (net (code "75") (name "unconnected-(U7-RTS#-Pad4)") (class "Default")
      (node (ref "U7") (pin "4") (pinfunction "RTS#_4") (pintype "passive+no_connect"))
    )
    (net (code "76") (name "unconnected-(USB1-SBU1-PadA8)") (class "Default")
      (node (ref "USB1") (pin "A8") (pinfunction "SBU1_A8") (pintype "passive+no_connect"))
    )
    (net (code "77") (name "unconnected-(USB1-SBU2-PadB8)") (class "Default")
      (node (ref "USB1") (pin "B8") (pinfunction "SBU2_B8") (pintype "passive+no_connect"))
    )
  )
)
